# Sheet3.net
KiCad netlist of a schematic drawn in Altium Designer
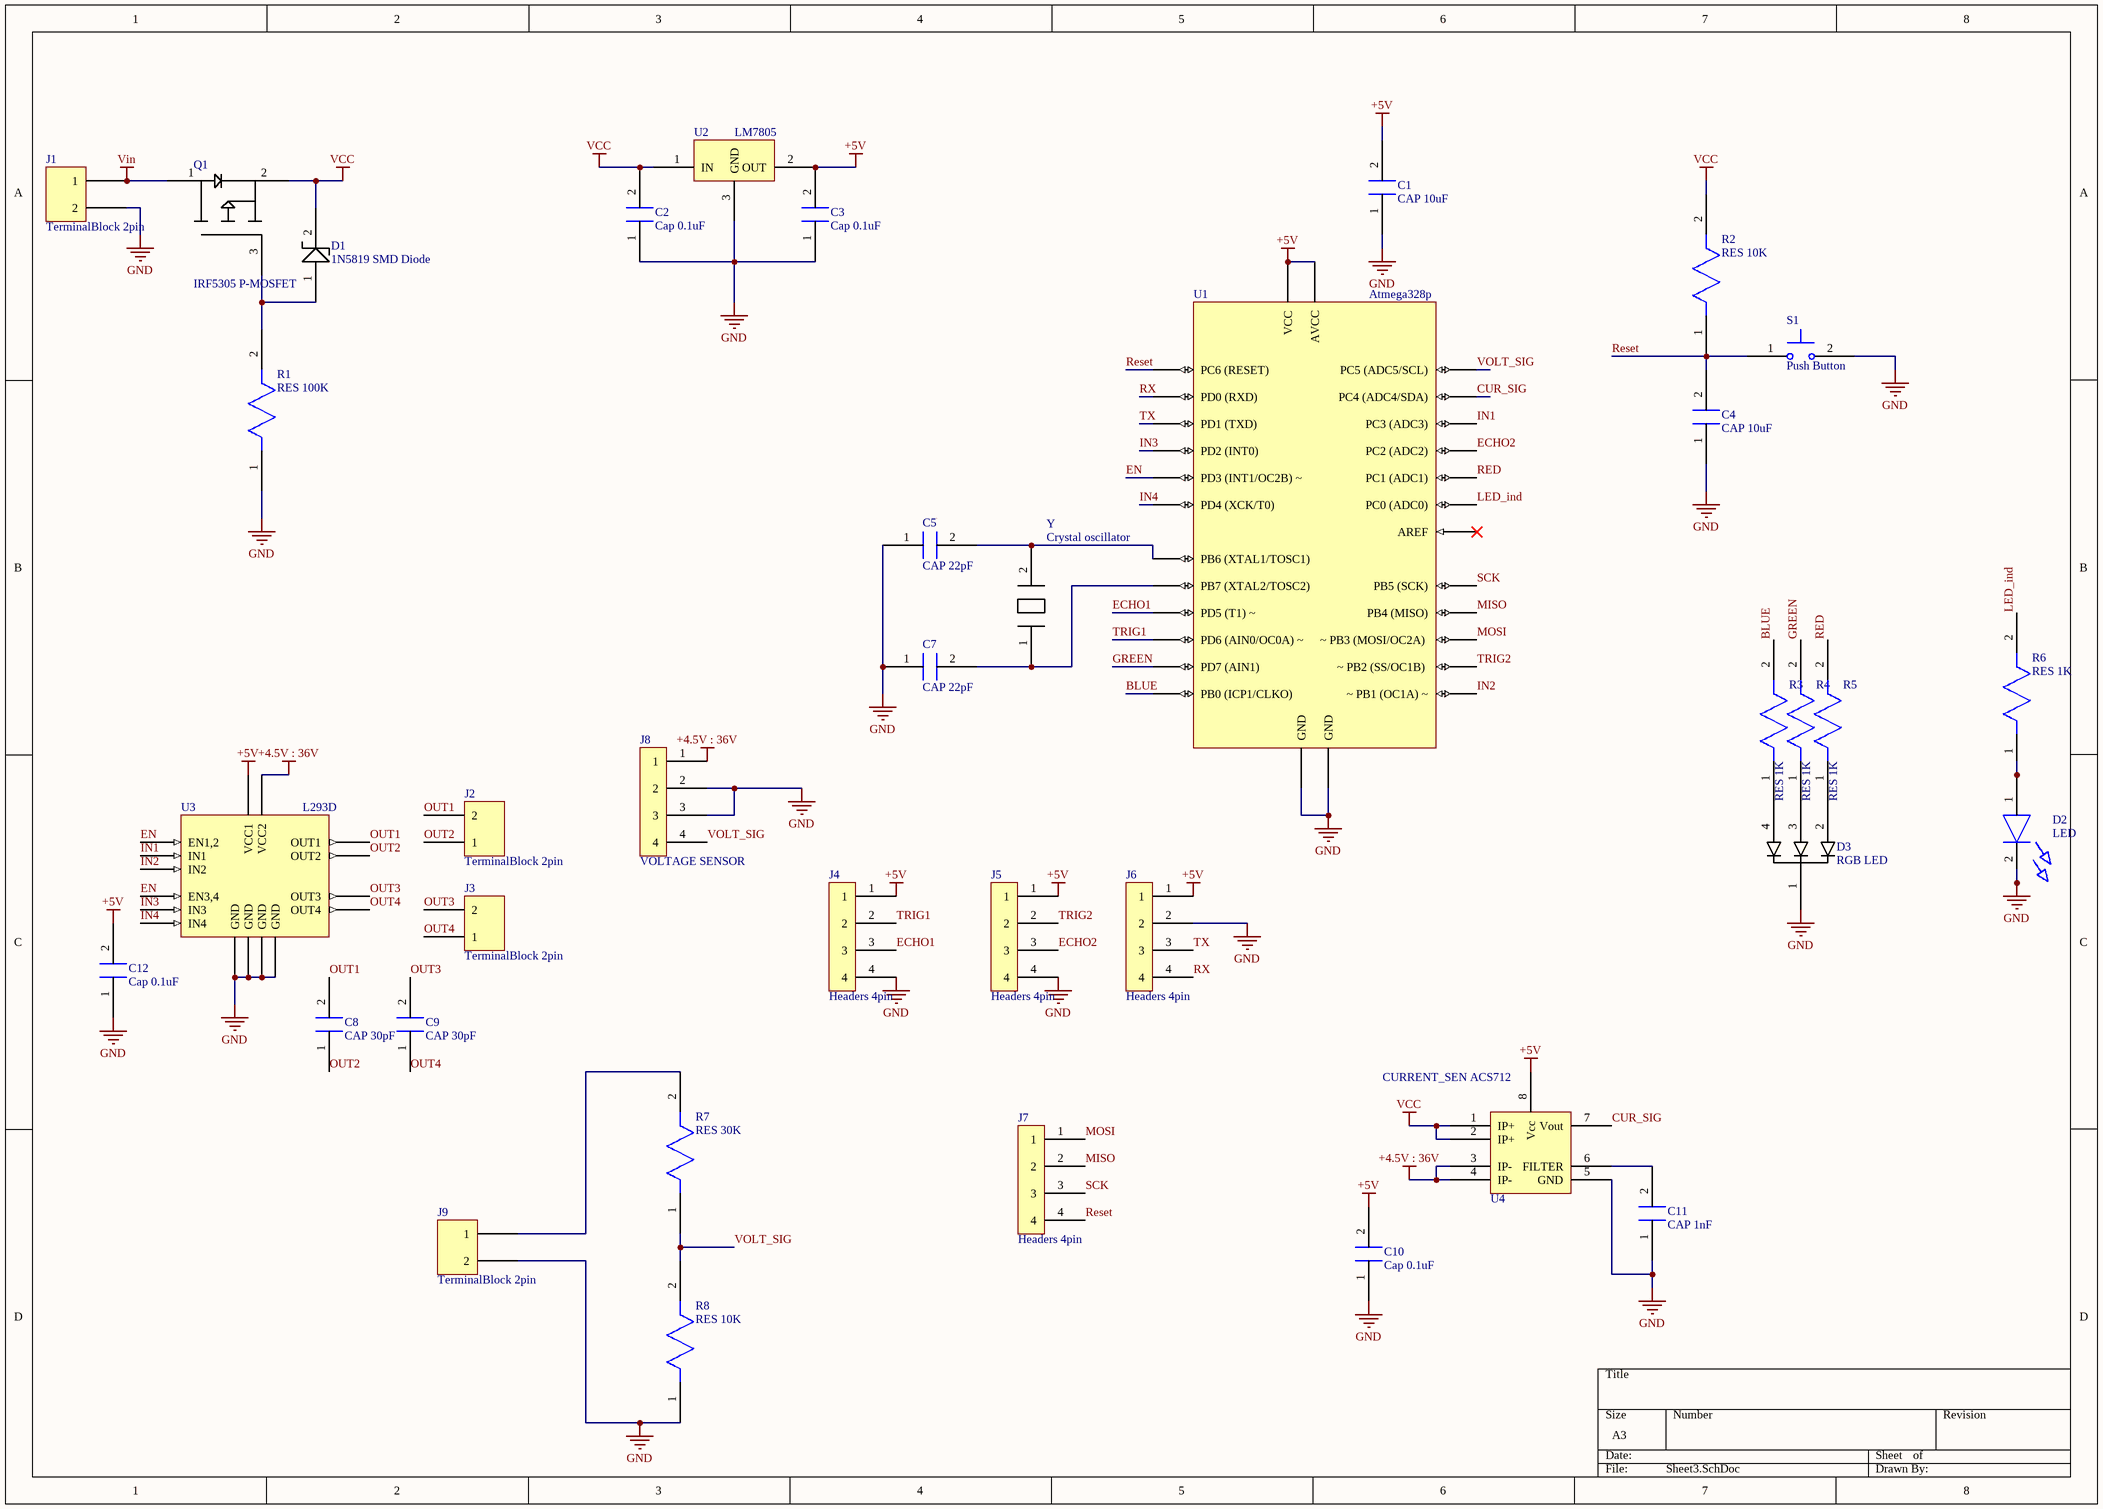
[diagram p0: Sheet3.SchDoc]

(export (version "E")
  (design (tool "Eeschema 10.0.6"))
  (components
    (comp (ref "C1") (value "CAP 10uF") (footprint "Cap 10uF") (libsource (lib "Schlib1") (part "CAP 10uF")))
    (comp (ref "C2")
      (value "Cap 0.1uF")
      (footprint "CAP 0.1uF")
      (libsource (lib "Schlib1") (part "Cap 0.1uF"))
    )
    (comp (ref "C3")
      (value "Cap 0.1uF")
      (footprint "CAP 0.1uF")
      (libsource (lib "Schlib1") (part "Cap 0.1uF"))
    )
    (comp (ref "C4") (value "CAP 10uF") (footprint "Cap 10uF") (libsource (lib "Schlib1") (part "CAP 10uF")))
    (comp (ref "C5") (value "CAP 22pF") (footprint "Cap 22pF") (libsource (lib "Schlib1") (part "CAP 22pF")))
    (comp (ref "C7") (value "CAP 22pF") (footprint "Cap 22pF") (libsource (lib "Schlib1") (part "CAP 22pF")))
    (comp (ref "C8") (value "CAP 30pF") (footprint "CAP 30pF") (libsource (lib "Schlib1") (part "CAP 30pF")))
    (comp (ref "C9") (value "CAP 30pF") (footprint "CAP 30pF") (libsource (lib "Schlib1") (part "CAP 30pF")))
    (comp (ref "C10")
      (value "Cap 0.1uF")
      (footprint "CAP 0.1uF")
      (libsource (lib "Schlib1") (part "Cap 0.1uF"))
    )
    (comp (ref "C11") (value "CAP 1nF") (footprint "CAP 1nF") (libsource (lib "Schlib1") (part "CAP 1nF")))
    (comp (ref "C12")
      (value "Cap 0.1uF")
      (footprint "CAP 0.1uF")
      (libsource (lib "Schlib1") (part "Cap 0.1uF"))
    )
    (comp (ref "D1")
      (value "1N5819 SMD Diode")
      (footprint "1N5819 SMD Diode")
      (libsource (lib "Schlib1") (part "1N5819 SMD Diode"))
    )
    (comp (ref "D2") (value "LED") (footprint "LED") (libsource (lib "Schlib1") (part "LED")))
    (comp (ref "D3") (value "RGB LED") (footprint "RGB LED") (libsource (lib "Schlib1") (part "RGB LED")))
    (comp (ref "J1")
      (value "TerminalBlock 2pin")
      (footprint "Terminal Block 2pin")
      (libsource (lib "") (part "TerminalBlock 2pin_1"))
    )
    (comp (ref "J2")
      (value "TerminalBlock 2pin")
      (footprint "Terminal Block 2pin")
      (libsource (lib "Schlib1") (part "TerminalBlock 2pin"))
    )
    (comp (ref "J3")
      (value "TerminalBlock 2pin")
      (footprint "Terminal Block 2pin")
      (libsource (lib "Schlib1") (part "TerminalBlock 2pin"))
    )
    (comp (ref "J4")
      (value "Headers 4pin")
      (footprint "Header 4pin")
      (libsource (lib "Schlib1") (part "Headers 4pin"))
    )
    (comp (ref "J5")
      (value "Headers 4pin")
      (footprint "Header 4pin")
      (libsource (lib "Schlib1") (part "Headers 4pin"))
    )
    (comp (ref "J6")
      (value "Headers 4pin")
      (footprint "Header 4pin")
      (libsource (lib "Schlib1") (part "Headers 4pin"))
    )
    (comp (ref "J7")
      (value "Headers 4pin")
      (footprint "Header 4pin")
      (libsource (lib "Schlib1") (part "Headers 4pin"))
    )
    (comp (ref "J8")
      (value "VOLTAGE SENSOR")
      (footprint "Header 4pin")
      (libsource (lib "Schlib1") (part "Headers 4pin"))
    )
    (comp (ref "J9")
      (value "TerminalBlock 2pin")
      (footprint "Terminal Block 2pin")
      (libsource (lib "") (part "TerminalBlock 2pin_1"))
    )
    (comp (ref "Q1")
      (value "IRF5305 P-MOSFET")
      (footprint "IRF5305")
      (libsource (lib "Schlib1") (part "IRF5305 P-MOSFET"))
    )
    (comp (ref "R1") (value "RES 100K") (footprint "Res100K") (libsource (lib "Schlib1") (part "RES 100K")))
    (comp (ref "R2") (value "RES 10K") (footprint "Res10K") (libsource (lib "Schlib1") (part "RES 10K")))
    (comp (ref "R3") (value "RES 1K") (footprint "Res 1K") (libsource (lib "Schlib1") (part "RES 1K")))
    (comp (ref "R4") (value "RES 1K") (footprint "Res 1K") (libsource (lib "Schlib1") (part "RES 1K")))
    (comp (ref "R5") (value "RES 1K") (footprint "Res 1K") (libsource (lib "Schlib1") (part "RES 1K")))
    (comp (ref "R6") (value "RES 1K") (footprint "Res 1K") (libsource (lib "Schlib1") (part "RES 1K")))
    (comp (ref "R7") (value "RES 30K") (footprint "Res100K") (libsource (lib "Schlib1") (part "RES 100K")))
    (comp (ref "R8") (value "RES 10K") (footprint "Res10K") (libsource (lib "Schlib1") (part "RES 10K")))
    (comp (ref "S1")
      (value "Push Button")
      (footprint "Push Button")
      (libsource (lib "Schlib1") (part "Push Button"))
    )
    (comp (ref "U1")
      (value "Atmega328p")
      (footprint "ATMega 328 P-PU - duplicate")
      (libsource (lib "Schlib1") (part "Atmega328p"))
    )
    (comp (ref "U2") (value "LM7805") (footprint "LM7805") (libsource (lib "Schlib1") (part "LM7805")))
    (comp (ref "U3") (value "L293D") (footprint "L293D") (libsource (lib "Schlib1") (part "L293D")))
    (comp (ref "U4")
      (value "CURRENT_SEN ACS712")
      (footprint "Cuurent_sens")
      (libsource (lib "Schlib1") (part "CURRENT_MOD ACS712"))
    )
    (comp (ref "Y")
      (value "Crystal oscillator")
      (footprint "Crrystal 16MHZ")
      (libsource (lib "Schlib1") (part "Crystal oscillator"))
    )
  )
  (nets
    (net (code "1") (name "+4.5V : 36V") (class "Default")
      (node (ref "J8") (pin "1") (pinfunction "1_1") (pintype "passive"))
      (node (ref "U3") (pin "8") (pinfunction "VCC2_8") (pintype "power_in"))
      (node (ref "U4") (pin "3") (pinfunction "IP-_3") (pintype "passive"))
      (node (ref "U4") (pin "4") (pinfunction "IP-_4") (pintype "passive"))
    )
    (net (code "2") (name "+5V") (class "Default")
      (node (ref "C1") (pin "2") (pinfunction "2_2") (pintype "passive"))
      (node (ref "C10") (pin "2") (pinfunction "2_2") (pintype "passive"))
      (node (ref "C12") (pin "2") (pinfunction "2_2") (pintype "passive"))
      (node (ref "C3") (pin "2") (pinfunction "2_2") (pintype "passive"))
      (node (ref "J4") (pin "1") (pinfunction "1_1") (pintype "passive"))
      (node (ref "J5") (pin "1") (pinfunction "1_1") (pintype "passive"))
      (node (ref "J6") (pin "1") (pinfunction "1_1") (pintype "passive"))
      (node (ref "U1") (pin "20") (pinfunction "AVCC_20") (pintype "passive"))
      (node (ref "U1") (pin "7") (pinfunction "VCC_7") (pintype "passive"))
      (node (ref "U2") (pin "2") (pinfunction "OUT_2") (pintype "passive"))
      (node (ref "U3") (pin "16") (pinfunction "VCC1_16") (pintype "power_in"))
      (node (ref "U4") (pin "8") (pinfunction "Vcc_8") (pintype "passive"))
    )
    (net (code "4") (name "/BLUE") (class "Default")
      (node (ref "R3") (pin "2") (pinfunction "4_2") (pintype "passive"))
      (node (ref "U1") (pin "14") (pinfunction "PB0_(ICP1/CLKO)_14") (pintype "bidirectional"))
    )
    (net (code "5") (name "/CUR_SIG") (class "Default")
      (node (ref "U1") (pin "27") (pinfunction "PC4_(ADC4/SDA)_27") (pintype "bidirectional"))
      (node (ref "U4") (pin "7") (pinfunction "Vout_7") (pintype "passive"))
    )
    (net (code "6") (name "/ECHO1") (class "Default")
      (node (ref "J4") (pin "3") (pinfunction "3_3") (pintype "passive"))
      (node (ref "U1") (pin "11") (pinfunction "PD5_(T1)_~_11") (pintype "bidirectional"))
    )
    (net (code "7") (name "/ECHO2") (class "Default")
      (node (ref "J5") (pin "3") (pinfunction "3_3") (pintype "passive"))
      (node (ref "U1") (pin "25") (pinfunction "PC2_(ADC2)_25") (pintype "bidirectional"))
    )
    (net (code "8") (name "/EN") (class "Default")
      (node (ref "U1") (pin "5") (pinfunction "PD3_(INT1/OC2B)_~_5") (pintype "bidirectional"))
      (node (ref "U3") (pin "1") (pinfunction "EN1,2_1") (pintype "input"))
      (node (ref "U3") (pin "9") (pinfunction "EN3,4_9") (pintype "input"))
    )
    (net (code "9") (name "/GREEN") (class "Default")
      (node (ref "R4") (pin "2") (pinfunction "4_2") (pintype "passive"))
      (node (ref "U1") (pin "13") (pinfunction "PD7_(AIN1)_13") (pintype "bidirectional"))
    )
    (net (code "10") (name "/IN1") (class "Default")
      (node (ref "U1") (pin "26") (pinfunction "PC3_(ADC3)_26") (pintype "bidirectional"))
      (node (ref "U3") (pin "2") (pinfunction "IN1_2") (pintype "input"))
    )
    (net (code "11") (name "/IN2") (class "Default")
      (node (ref "U1") (pin "15") (pinfunction "~_PB1_(OC1A)_~_15") (pintype "bidirectional"))
      (node (ref "U3") (pin "7") (pinfunction "IN2_7") (pintype "input"))
    )
    (net (code "12") (name "/IN3") (class "Default")
      (node (ref "U1") (pin "4") (pinfunction "PD2_(INT0)_4") (pintype "bidirectional"))
      (node (ref "U3") (pin "10") (pinfunction "IN3_10") (pintype "input"))
    )
    (net (code "13") (name "/IN4") (class "Default")
      (node (ref "U1") (pin "6") (pinfunction "PD4_(XCK/T0)_6") (pintype "bidirectional"))
      (node (ref "U3") (pin "15") (pinfunction "IN4_15") (pintype "input"))
    )
    (net (code "14") (name "/LED_ind") (class "Default")
      (node (ref "R6") (pin "2") (pinfunction "4_2") (pintype "passive"))
      (node (ref "U1") (pin "23") (pinfunction "PC0_(ADC0)_23") (pintype "bidirectional"))
    )
    (net (code "15") (name "/MISO") (class "Default")
      (node (ref "J7") (pin "2") (pinfunction "2_2") (pintype "passive"))
      (node (ref "U1") (pin "18") (pinfunction "PB4_(MISO)_18") (pintype "bidirectional"))
    )
    (net (code "16") (name "/MOSI") (class "Default")
      (node (ref "J7") (pin "1") (pinfunction "1_1") (pintype "passive"))
      (node (ref "U1") (pin "17") (pinfunction "~_PB3_(MOSI/OC2A)_17") (pintype "bidirectional"))
    )
    (net (code "17") (name "/OUT1") (class "Default")
      (node (ref "C8") (pin "2") (pinfunction "2_2") (pintype "passive"))
      (node (ref "J2") (pin "2") (pinfunction "2_2") (pintype "passive"))
      (node (ref "U3") (pin "3") (pinfunction "OUT1_3") (pintype "output"))
    )
    (net (code "18") (name "/OUT2") (class "Default")
      (node (ref "C8") (pin "1") (pinfunction "1_1") (pintype "passive"))
      (node (ref "J2") (pin "1") (pinfunction "1_1") (pintype "passive"))
      (node (ref "U3") (pin "6") (pinfunction "OUT2_6") (pintype "output"))
    )
    (net (code "19") (name "/OUT3") (class "Default")
      (node (ref "C9") (pin "2") (pinfunction "2_2") (pintype "passive"))
      (node (ref "J3") (pin "2") (pinfunction "2_2") (pintype "passive"))
      (node (ref "U3") (pin "11") (pinfunction "OUT3_11") (pintype "output"))
    )
    (net (code "20") (name "/OUT4") (class "Default")
      (node (ref "C9") (pin "1") (pinfunction "1_1") (pintype "passive"))
      (node (ref "J3") (pin "1") (pinfunction "1_1") (pintype "passive"))
      (node (ref "U3") (pin "14") (pinfunction "OUT4_14") (pintype "output"))
    )
    (net (code "21") (name "/RED") (class "Default")
      (node (ref "R5") (pin "2") (pinfunction "4_2") (pintype "passive"))
      (node (ref "U1") (pin "24") (pinfunction "PC1_(ADC1)_24") (pintype "bidirectional"))
    )
    (net (code "22") (name "/RX") (class "Default")
      (node (ref "J6") (pin "4") (pinfunction "4_4") (pintype "passive"))
      (node (ref "U1") (pin "2") (pinfunction "PD0_(RXD)_2") (pintype "bidirectional"))
    )
    (net (code "23") (name "/Reset") (class "Default")
      (node (ref "C4") (pin "2") (pinfunction "2_2") (pintype "passive"))
      (node (ref "J7") (pin "4") (pinfunction "4_4") (pintype "passive"))
      (node (ref "R2") (pin "1") (pinfunction "3_1") (pintype "passive"))
      (node (ref "S1") (pin "1") (pinfunction "76_1") (pintype "passive"))
      (node (ref "U1") (pin "1") (pinfunction "PC6_(RESET)_1") (pintype "bidirectional"))
    )
    (net (code "24") (name "/SCK") (class "Default")
      (node (ref "J7") (pin "3") (pinfunction "3_3") (pintype "passive"))
      (node (ref "U1") (pin "19") (pinfunction "PB5_(SCK)_19") (pintype "bidirectional"))
    )
    (net (code "25") (name "/TRIG1") (class "Default")
      (node (ref "J4") (pin "2") (pinfunction "2_2") (pintype "passive"))
      (node (ref "U1") (pin "12") (pinfunction "PD6_(AIN0/OC0A)_~_12") (pintype "bidirectional"))
    )
    (net (code "26") (name "/TRIG2") (class "Default")
      (node (ref "J5") (pin "2") (pinfunction "2_2") (pintype "passive"))
      (node (ref "U1") (pin "16") (pinfunction "~_PB2_(SS/OC1B)_16") (pintype "bidirectional"))
    )
    (net (code "27") (name "/TX") (class "Default")
      (node (ref "J6") (pin "3") (pinfunction "3_3") (pintype "passive"))
      (node (ref "U1") (pin "3") (pinfunction "PD1_(TXD)_3") (pintype "bidirectional"))
    )
    (net (code "28") (name "/VOLT_SIG") (class "Default")
      (node (ref "J8") (pin "4") (pinfunction "4_4") (pintype "passive"))
      (node (ref "R7") (pin "1") (pinfunction "3_1") (pintype "passive"))
      (node (ref "R8") (pin "2") (pinfunction "4_2") (pintype "passive"))
      (node (ref "U1") (pin "28") (pinfunction "PC5_(ADC5/SCL)_28") (pintype "bidirectional"))
    )
    (net (code "29") (name "GND") (class "Default")
      (node (ref "C1") (pin "1") (pinfunction "1_1") (pintype "passive"))
      (node (ref "C10") (pin "1") (pinfunction "1_1") (pintype "passive"))
      (node (ref "C11") (pin "1") (pinfunction "1_1") (pintype "passive"))
      (node (ref "C12") (pin "1") (pinfunction "1_1") (pintype "passive"))
      (node (ref "C2") (pin "1") (pinfunction "1_1") (pintype "passive"))
      (node (ref "C3") (pin "1") (pinfunction "1_1") (pintype "passive"))
      (node (ref "C4") (pin "1") (pinfunction "1_1") (pintype "passive"))
      (node (ref "C5") (pin "1") (pinfunction "1_1") (pintype "passive"))
      (node (ref "C7") (pin "1") (pinfunction "1_1") (pintype "passive"))
      (node (ref "D2") (pin "2") (pinfunction "6_2") (pintype "passive"))
      (node (ref "D3") (pin "1") (pinfunction "(-)_1") (pintype "passive"))
      (node (ref "J1") (pin "2") (pinfunction "2_2") (pintype "passive"))
      (node (ref "J4") (pin "4") (pinfunction "4_4") (pintype "passive"))
      (node (ref "J5") (pin "4") (pinfunction "4_4") (pintype "passive"))
      (node (ref "J6") (pin "2") (pinfunction "2_2") (pintype "passive"))
      (node (ref "J8") (pin "2") (pinfunction "2_2") (pintype "passive"))
      (node (ref "J8") (pin "3") (pinfunction "3_3") (pintype "passive"))
      (node (ref "J9") (pin "2") (pinfunction "2_2") (pintype "passive"))
      (node (ref "R1") (pin "1") (pinfunction "3_1") (pintype "passive"))
      (node (ref "R8") (pin "1") (pinfunction "3_1") (pintype "passive"))
      (node (ref "S1") (pin "2") (pinfunction "77_2") (pintype "passive"))
      (node (ref "U1") (pin "22") (pinfunction "GND_22") (pintype "passive"))
      (node (ref "U1") (pin "8") (pinfunction "GND_8") (pintype "passive"))
      (node (ref "U2") (pin "3") (pinfunction "GND_3") (pintype "power_in"))
      (node (ref "U3") (pin "12") (pinfunction "GND_12") (pintype "power_in"))
      (node (ref "U3") (pin "13") (pinfunction "GND_13") (pintype "power_in"))
      (node (ref "U3") (pin "4") (pinfunction "GND_4") (pintype "power_in"))
      (node (ref "U3") (pin "5") (pinfunction "GND_5") (pintype "power_in"))
      (node (ref "U4") (pin "5") (pinfunction "GND_5") (pintype "passive"))
    )
    (net (code "30") (name "Net-(D2-7)") (class "Default")
      (node (ref "D2") (pin "1") (pinfunction "7_1") (pintype "passive"))
      (node (ref "R6") (pin "1") (pinfunction "3_1") (pintype "passive"))
    )
    (net (code "31") (name "Net-(D3-B)") (class "Default")
      (node (ref "D3") (pin "4") (pinfunction "B_4") (pintype "passive"))
      (node (ref "R3") (pin "1") (pinfunction "3_1") (pintype "passive"))
    )
    (net (code "32") (name "Net-(D3-G)") (class "Default")
      (node (ref "D3") (pin "3") (pinfunction "G_3") (pintype "passive"))
      (node (ref "R4") (pin "1") (pinfunction "3_1") (pintype "passive"))
    )
    (net (code "33") (name "Net-(D3-R)") (class "Default")
      (node (ref "D3") (pin "2") (pinfunction "R_2") (pintype "passive"))
      (node (ref "R5") (pin "1") (pinfunction "3_1") (pintype "passive"))
    )
    (net (code "34") (name "Net-(Q1-G)") (class "Default")
      (node (ref "D1") (pin "1") (pinfunction "1_1") (pintype "passive"))
      (node (ref "Q1") (pin "3") (pinfunction "G_3") (pintype "passive"))
      (node (ref "R1") (pin "2") (pinfunction "4_2") (pintype "passive"))
    )
    (net (code "35") (name "Net-(R7-4)") (class "Default")
      (node (ref "J9") (pin "1") (pinfunction "1_1") (pintype "passive"))
      (node (ref "R7") (pin "2") (pinfunction "4_2") (pintype "passive"))
    )
    (net (code "36") (name "Net-(U1-PB6_(XTAL1{slash}TOSC1))") (class "Default")
      (node (ref "C5") (pin "2") (pinfunction "2_2") (pintype "passive"))
      (node (ref "U1") (pin "9") (pinfunction "PB6_(XTAL1/TOSC1)_9") (pintype "bidirectional"))
      (node (ref "Y") (pin "2") (pinfunction "2_2") (pintype "passive"))
    )
    (net (code "37") (name "Net-(U1-PB7_(XTAL2{slash}TOSC2))") (class "Default")
      (node (ref "C7") (pin "2") (pinfunction "2_2") (pintype "passive"))
      (node (ref "U1") (pin "10") (pinfunction "PB7_(XTAL2/TOSC2)_10") (pintype "bidirectional"))
      (node (ref "Y") (pin "1") (pinfunction "1_1") (pintype "passive"))
    )
    (net (code "38") (name "Net-(U4-FILTER)") (class "Default")
      (node (ref "C11") (pin "2") (pinfunction "2_2") (pintype "passive"))
      (node (ref "U4") (pin "6") (pinfunction "FILTER_6") (pintype "passive"))
    )
    (net (code "39") (name "VCC") (class "Default")
      (node (ref "C2") (pin "2") (pinfunction "2_2") (pintype "passive"))
      (node (ref "D1") (pin "2") (pinfunction "2_2") (pintype "passive"))
      (node (ref "Q1") (pin "2") (pinfunction "S_2") (pintype "passive"))
      (node (ref "R2") (pin "2") (pinfunction "4_2") (pintype "passive"))
      (node (ref "U2") (pin "1") (pinfunction "IN_1") (pintype "passive"))
      (node (ref "U4") (pin "1") (pinfunction "IP+_1") (pintype "passive"))
      (node (ref "U4") (pin "2") (pinfunction "IP+_2") (pintype "passive"))
    )
    (net (code "40") (name "Vin") (class "Default")
      (node (ref "J1") (pin "1") (pinfunction "1_1") (pintype "passive"))
      (node (ref "Q1") (pin "1") (pinfunction "D_1") (pintype "passive"))
    )
    (net (code "41") (name "unconnected-(U1-AREF-Pad21)") (class "Default")
      (node (ref "U1") (pin "21") (pinfunction "AREF_21") (pintype "input+no_connect"))
    )
  )
)
